# V1.net
KiCad netlist of a schematic drawn in EAGLE
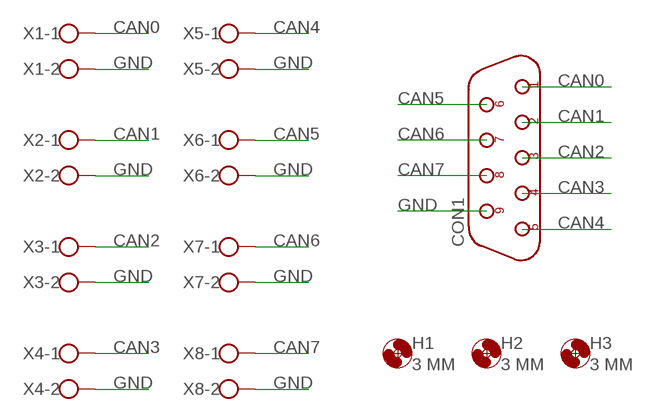
[diagram p0: schematic, sheet 1]

(export (version "E")
  (design (tool "Eeschema 10.0.6"))
  (components
    (comp (ref "CON1")
      (value "DB9F/90")
      (footprint "eagle-import:D-09F_90")
      (libsource (lib "eagle-import") (part "DB9F/90"))
    )
    (comp (ref "H1")
      (value "3 MM")
      (footprint "eagle-import:3,0")
      (libsource (lib "eagle-import") (part "MOUNT-HOLE3.0"))
    )
    (comp (ref "H2")
      (value "3 MM")
      (footprint "eagle-import:3,0")
      (libsource (lib "eagle-import") (part "MOUNT-HOLE3.0"))
    )
    (comp (ref "H3")
      (value "3 MM")
      (footprint "eagle-import:3,0")
      (libsource (lib "eagle-import") (part "MOUNT-HOLE3.0"))
    )
    (comp (ref "X1")
      (value "W237-102")
      (footprint "eagle-import:W237-102")
      (fields (field (name "MPN") "237-102"))
      (libsource (lib "eagle-import") (part "W237-102"))
    )
    (comp (ref "X2")
      (value "W237-102")
      (footprint "eagle-import:W237-102")
      (fields (field (name "MPN") "237-102"))
      (libsource (lib "eagle-import") (part "W237-102"))
    )
    (comp (ref "X3")
      (value "W237-102")
      (footprint "eagle-import:W237-102")
      (fields (field (name "MPN") "237-102"))
      (libsource (lib "eagle-import") (part "W237-102"))
    )
    (comp (ref "X4")
      (value "W237-102")
      (footprint "eagle-import:W237-102")
      (fields (field (name "MPN") "237-102"))
      (libsource (lib "eagle-import") (part "W237-102"))
    )
    (comp (ref "X5")
      (value "W237-102")
      (footprint "eagle-import:W237-102")
      (fields (field (name "MPN") "237-102"))
      (libsource (lib "eagle-import") (part "W237-102"))
    )
    (comp (ref "X6")
      (value "W237-102")
      (footprint "eagle-import:W237-102")
      (fields (field (name "MPN") "237-102"))
      (libsource (lib "eagle-import") (part "W237-102"))
    )
    (comp (ref "X7")
      (value "W237-102")
      (footprint "eagle-import:W237-102")
      (fields (field (name "MPN") "237-102"))
      (libsource (lib "eagle-import") (part "W237-102"))
    )
    (comp (ref "X8")
      (value "W237-102")
      (footprint "eagle-import:W237-102")
      (fields (field (name "MPN") "237-102"))
      (libsource (lib "eagle-import") (part "W237-102"))
    )
  )
  (nets
    (net (code "1") (name "/CAN0") (class "Default")
      (node (ref "CON1") (pin "1") (pinfunction "1_1") (pintype "passive"))
      (node (ref "X1") (pin "1") (pinfunction "KL_1") (pintype "passive"))
    )
    (net (code "2") (name "/CAN1") (class "Default")
      (node (ref "CON1") (pin "2") (pinfunction "2_2") (pintype "passive"))
      (node (ref "X2") (pin "1") (pinfunction "KL_1") (pintype "passive"))
    )
    (net (code "3") (name "/CAN2") (class "Default")
      (node (ref "CON1") (pin "3") (pinfunction "3_3") (pintype "passive"))
      (node (ref "X3") (pin "1") (pinfunction "KL_1") (pintype "passive"))
    )
    (net (code "4") (name "/CAN3") (class "Default")
      (node (ref "CON1") (pin "4") (pinfunction "4_4") (pintype "passive"))
      (node (ref "X4") (pin "1") (pinfunction "KL_1") (pintype "passive"))
    )
    (net (code "5") (name "/CAN4") (class "Default")
      (node (ref "CON1") (pin "5") (pinfunction "5_5") (pintype "passive"))
      (node (ref "X5") (pin "1") (pinfunction "KL_1") (pintype "passive"))
    )
    (net (code "6") (name "/CAN5") (class "Default")
      (node (ref "CON1") (pin "6") (pinfunction "6_6") (pintype "passive"))
      (node (ref "X6") (pin "1") (pinfunction "KL_1") (pintype "passive"))
    )
    (net (code "7") (name "/CAN6") (class "Default")
      (node (ref "CON1") (pin "7") (pinfunction "7_7") (pintype "passive"))
      (node (ref "X7") (pin "1") (pinfunction "KL_1") (pintype "passive"))
    )
    (net (code "8") (name "/CAN7") (class "Default")
      (node (ref "CON1") (pin "8") (pinfunction "8_8") (pintype "passive"))
      (node (ref "X8") (pin "1") (pinfunction "KL_1") (pintype "passive"))
    )
    (net (code "9") (name "/GND") (class "Default")
      (node (ref "CON1") (pin "9") (pinfunction "9_9") (pintype "passive"))
      (node (ref "X1") (pin "2") (pinfunction "KL_2") (pintype "passive"))
      (node (ref "X2") (pin "2") (pinfunction "KL_2") (pintype "passive"))
      (node (ref "X3") (pin "2") (pinfunction "KL_2") (pintype "passive"))
      (node (ref "X4") (pin "2") (pinfunction "KL_2") (pintype "passive"))
      (node (ref "X5") (pin "2") (pinfunction "KL_2") (pintype "passive"))
      (node (ref "X6") (pin "2") (pinfunction "KL_2") (pintype "passive"))
      (node (ref "X7") (pin "2") (pinfunction "KL_2") (pintype "passive"))
      (node (ref "X8") (pin "2") (pinfunction "KL_2") (pintype "passive"))
    )
  )
)
